# TeensyBreakout.net
KiCad netlist of a schematic drawn in EAGLE
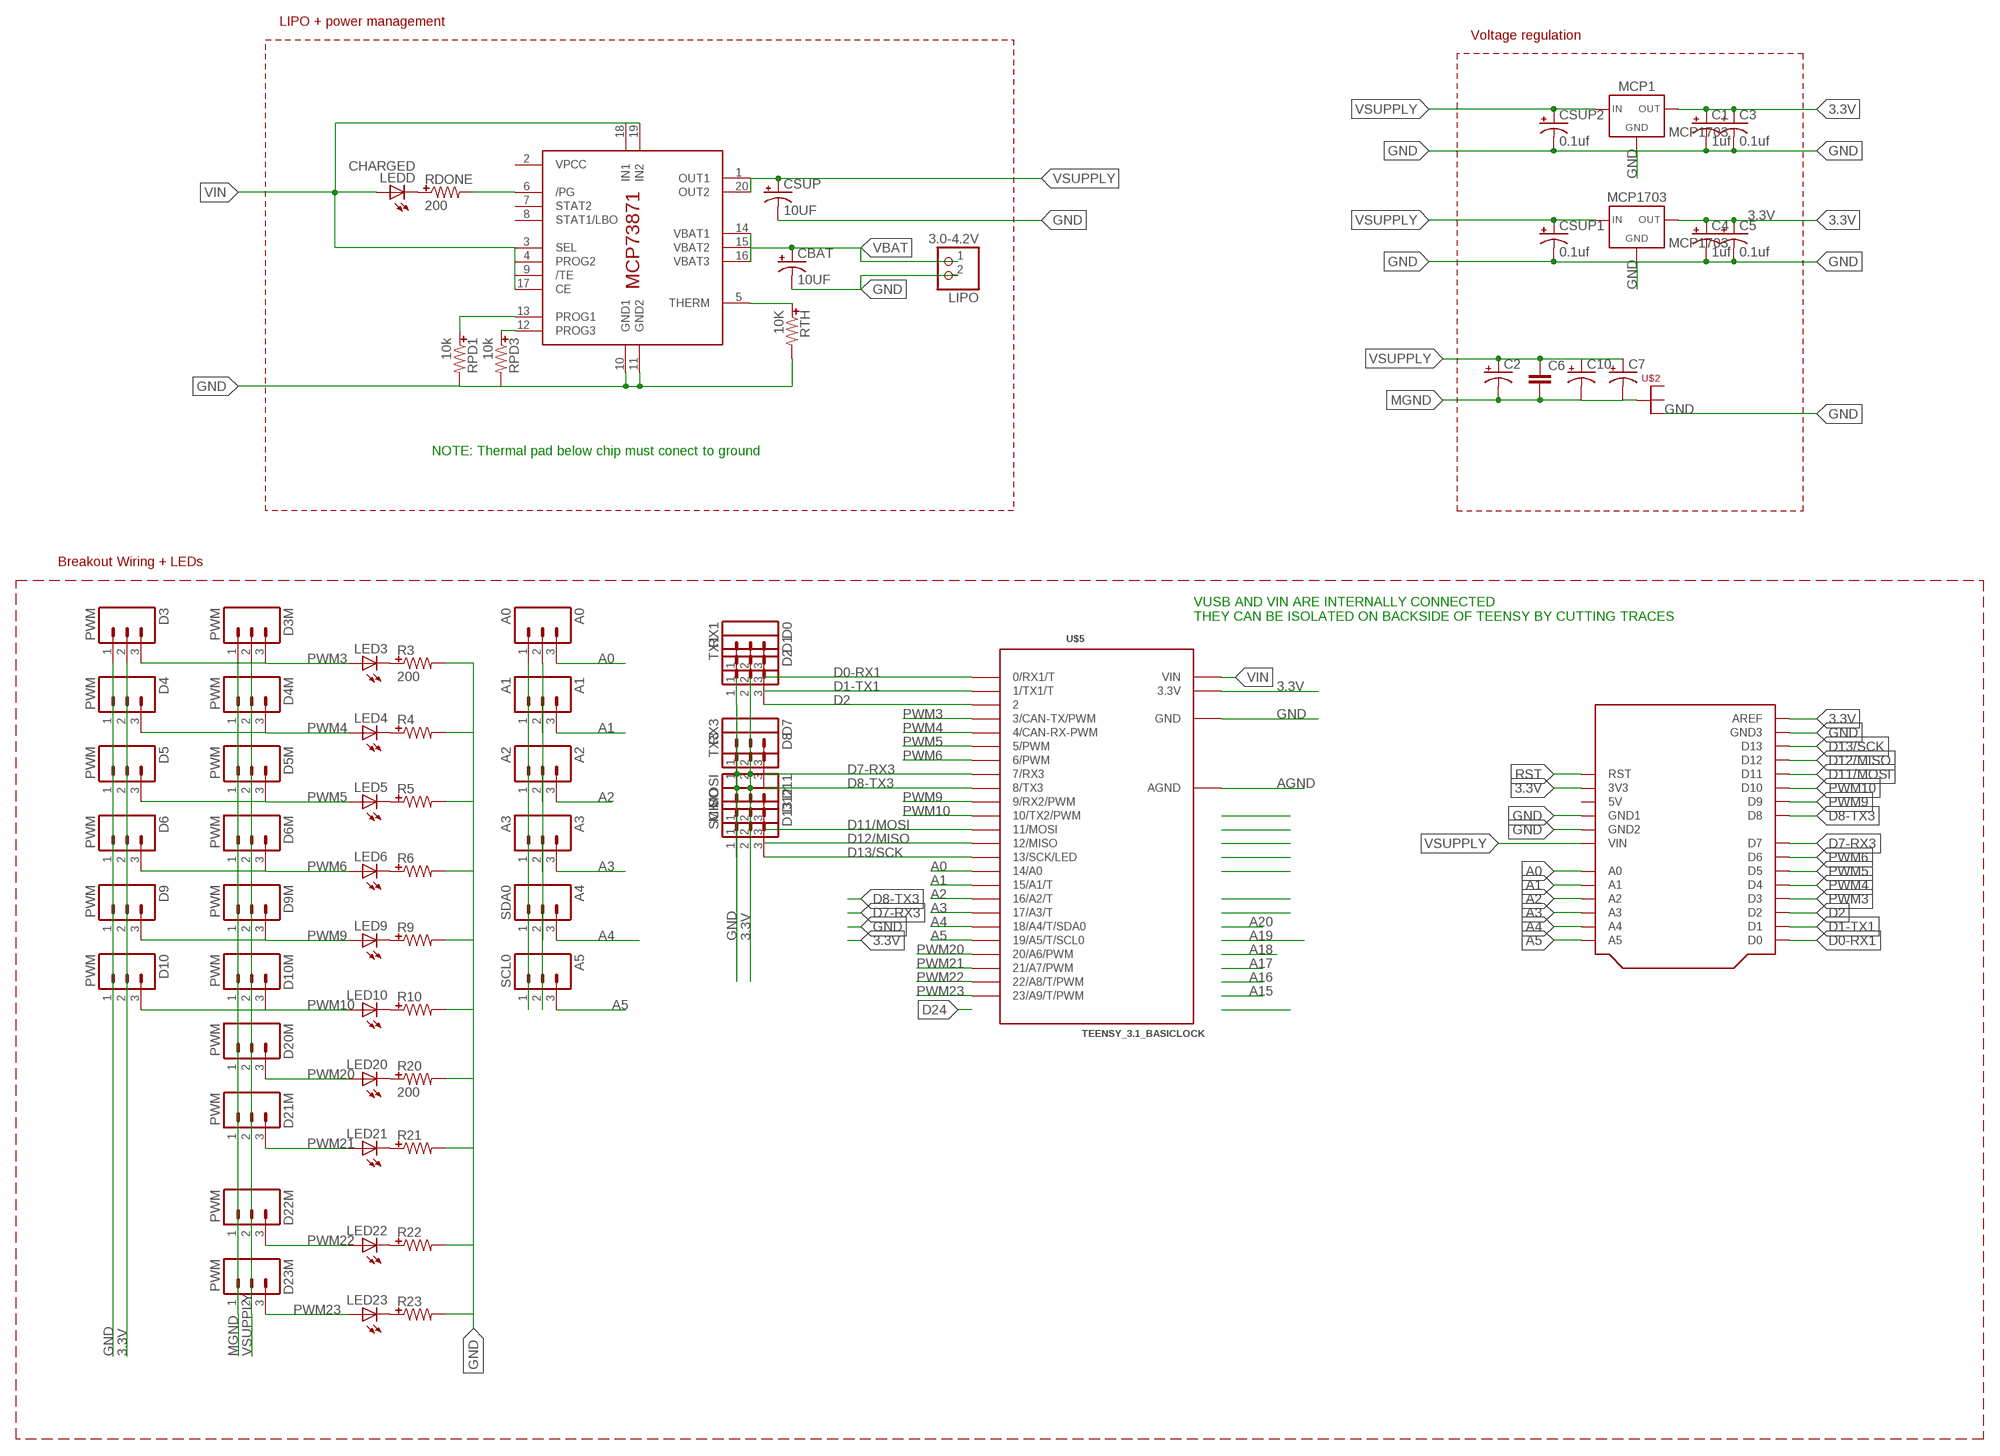
[diagram p0: schematic, sheet 1]

(export (version "E")
  (design (tool "Eeschema 10.0.6"))
  (components
    (comp (ref "A0")
      (value "A0")
      (footprint "eagle-import:1X03_LOCK")
      (libsource (lib "eagle-import") (part "M03LOCK"))
    )
    (comp (ref "A1")
      (value "A1")
      (footprint "eagle-import:1X03_LOCK")
      (libsource (lib "eagle-import") (part "M03LOCK"))
    )
    (comp (ref "A2")
      (value "A2")
      (footprint "eagle-import:1X03_LOCK")
      (libsource (lib "eagle-import") (part "M03LOCK"))
    )
    (comp (ref "A3")
      (value "A3")
      (footprint "eagle-import:1X03_LOCK")
      (libsource (lib "eagle-import") (part "M03LOCK"))
    )
    (comp (ref "A4")
      (value "SDA0")
      (footprint "eagle-import:1X03_LOCK")
      (libsource (lib "eagle-import") (part "M03LOCK"))
    )
    (comp (ref "A5")
      (value "SCL0")
      (footprint "eagle-import:1X03_LOCK")
      (libsource (lib "eagle-import") (part "M03LOCK"))
    )
    (comp (ref "C1")
      (value "1uf")
      (footprint "eagle-import:0402-0603-0805-UNIVERSAL")
      (libsource (lib "eagle-import") (part "CAP-POLARIZEDUNIVERSAL"))
    )
    (comp (ref "C2")
      (value "CAP-POLARIZEDUNIVERSAL")
      (footprint "eagle-import:0402-0603-0805-UNIVERSAL")
      (libsource (lib "eagle-import") (part "CAP-POLARIZEDUNIVERSAL"))
    )
    (comp (ref "C3")
      (value "0.1uf")
      (footprint "eagle-import:0402-0603-0805-UNIVERSAL")
      (libsource (lib "eagle-import") (part "CAP-POLARIZEDUNIVERSAL"))
    )
    (comp (ref "C4")
      (value "1uf")
      (footprint "eagle-import:0402-0603-0805-UNIVERSAL")
      (libsource (lib "eagle-import") (part "CAP-POLARIZEDUNIVERSAL"))
    )
    (comp (ref "C5")
      (value "0.1uf")
      (footprint "eagle-import:0402-0603-0805-UNIVERSAL")
      (libsource (lib "eagle-import") (part "CAP-POLARIZEDUNIVERSAL"))
    )
    (comp (ref "C6")
      (value "CAP1210")
      (footprint "eagle-import:1210")
      (libsource (lib "eagle-import") (part "CAP1210"))
    )
    (comp (ref "C7")
      (value "CAP-POLARIZEDUNIVERSAL")
      (footprint "eagle-import:0402-0603-0805-UNIVERSAL")
      (libsource (lib "eagle-import") (part "CAP-POLARIZEDUNIVERSAL"))
    )
    (comp (ref "C10")
      (value "CAP-POLARIZEDUNIVERSAL")
      (footprint "eagle-import:0402-0603-0805-UNIVERSAL")
      (libsource (lib "eagle-import") (part "CAP-POLARIZEDUNIVERSAL"))
    )
    (comp (ref "CBAT")
      (value "10UF")
      (footprint "eagle-import:0402-0603-0805-UNIVERSAL")
      (libsource (lib "eagle-import") (part "CAP-POLARIZEDUNIVERSAL"))
    )
    (comp (ref "CSUP")
      (value "10UF")
      (footprint "eagle-import:0402-0603-0805-UNIVERSAL")
      (libsource (lib "eagle-import") (part "CAP-POLARIZEDUNIVERSAL"))
    )
    (comp (ref "CSUP1")
      (value "0.1uf")
      (footprint "eagle-import:0402-0603-0805-UNIVERSAL")
      (libsource (lib "eagle-import") (part "CAP-POLARIZEDUNIVERSAL"))
    )
    (comp (ref "CSUP2")
      (value "0.1uf")
      (footprint "eagle-import:0402-0603-0805-UNIVERSAL")
      (libsource (lib "eagle-import") (part "CAP-POLARIZEDUNIVERSAL"))
    )
    (comp (ref "D0")
      (value "RX1")
      (footprint "eagle-import:1X03_LOCK")
      (libsource (lib "eagle-import") (part "M03LOCK"))
    )
    (comp (ref "D1")
      (value "TX1")
      (footprint "eagle-import:1X03_LOCK")
      (libsource (lib "eagle-import") (part "M03LOCK"))
    )
    (comp (ref "D2")
      (value "M03LOCK")
      (footprint "eagle-import:1X03_LOCK")
      (libsource (lib "eagle-import") (part "M03LOCK"))
    )
    (comp (ref "D3")
      (value "PWM")
      (footprint "eagle-import:1X03_LOCK")
      (libsource (lib "eagle-import") (part "M03LOCK"))
    )
    (comp (ref "D3M")
      (value "PWM")
      (footprint "eagle-import:1X03_LOCK")
      (libsource (lib "eagle-import") (part "M03LOCK"))
    )
    (comp (ref "D4")
      (value "PWM")
      (footprint "eagle-import:1X03_LOCK")
      (libsource (lib "eagle-import") (part "M03LOCK"))
    )
    (comp (ref "D4M")
      (value "PWM")
      (footprint "eagle-import:1X03_LOCK")
      (libsource (lib "eagle-import") (part "M03LOCK"))
    )
    (comp (ref "D5")
      (value "PWM")
      (footprint "eagle-import:1X03_LOCK")
      (libsource (lib "eagle-import") (part "M03LOCK"))
    )
    (comp (ref "D5M")
      (value "PWM")
      (footprint "eagle-import:1X03_LOCK")
      (libsource (lib "eagle-import") (part "M03LOCK"))
    )
    (comp (ref "D6")
      (value "PWM")
      (footprint "eagle-import:1X03_LOCK")
      (libsource (lib "eagle-import") (part "M03LOCK"))
    )
    (comp (ref "D6M")
      (value "PWM")
      (footprint "eagle-import:1X03_LOCK")
      (libsource (lib "eagle-import") (part "M03LOCK"))
    )
    (comp (ref "D7")
      (value "RX3")
      (footprint "eagle-import:1X03_LOCK")
      (libsource (lib "eagle-import") (part "M03LOCK"))
    )
    (comp (ref "D8")
      (value "TX3")
      (footprint "eagle-import:1X03_LOCK")
      (libsource (lib "eagle-import") (part "M03LOCK"))
    )
    (comp (ref "D9")
      (value "PWM")
      (footprint "eagle-import:1X03_LOCK")
      (libsource (lib "eagle-import") (part "M03LOCK"))
    )
    (comp (ref "D9M")
      (value "PWM")
      (footprint "eagle-import:1X03_LOCK")
      (libsource (lib "eagle-import") (part "M03LOCK"))
    )
    (comp (ref "D10")
      (value "PWM")
      (footprint "eagle-import:1X03_LOCK")
      (libsource (lib "eagle-import") (part "M03LOCK"))
    )
    (comp (ref "D10M")
      (value "PWM")
      (footprint "eagle-import:1X03_LOCK")
      (libsource (lib "eagle-import") (part "M03LOCK"))
    )
    (comp (ref "D11")
      (value "MOSI")
      (footprint "eagle-import:1X03_LOCK")
      (libsource (lib "eagle-import") (part "M03LOCK"))
    )
    (comp (ref "D12")
      (value "MISO")
      (footprint "eagle-import:1X03_LOCK")
      (libsource (lib "eagle-import") (part "M03LOCK"))
    )
    (comp (ref "D13")
      (value "SCK")
      (footprint "eagle-import:1X03_LOCK")
      (libsource (lib "eagle-import") (part "M03LOCK"))
    )
    (comp (ref "D20M")
      (value "PWM")
      (footprint "eagle-import:1X03_LOCK")
      (libsource (lib "eagle-import") (part "M03LOCK"))
    )
    (comp (ref "D21M")
      (value "PWM")
      (footprint "eagle-import:1X03_LOCK")
      (libsource (lib "eagle-import") (part "M03LOCK"))
    )
    (comp (ref "D22M")
      (value "PWM")
      (footprint "eagle-import:1X03_LOCK")
      (libsource (lib "eagle-import") (part "M03LOCK"))
    )
    (comp (ref "D23M")
      (value "PWM")
      (footprint "eagle-import:1X03_LOCK")
      (libsource (lib "eagle-import") (part "M03LOCK"))
    )
    (comp (ref "IC1")
      (value "MCP73871")
      (footprint "eagle-import:QFN20")
      (libsource (lib "eagle-import") (part "MCP73871"))
    )
    (comp (ref "LED3")
      (value "LEDUNIVERSAL")
      (footprint "eagle-import:0402-0603-0805-UNIVERSAL")
      (libsource (lib "eagle-import") (part "LEDUNIVERSAL"))
    )
    (comp (ref "LED4")
      (value "LEDUNIVERSAL")
      (footprint "eagle-import:0402-0603-0805-UNIVERSAL")
      (libsource (lib "eagle-import") (part "LEDUNIVERSAL"))
    )
    (comp (ref "LED5")
      (value "LEDUNIVERSAL")
      (footprint "eagle-import:0402-0603-0805-UNIVERSAL")
      (libsource (lib "eagle-import") (part "LEDUNIVERSAL"))
    )
    (comp (ref "LED6")
      (value "LEDUNIVERSAL")
      (footprint "eagle-import:0402-0603-0805-UNIVERSAL")
      (libsource (lib "eagle-import") (part "LEDUNIVERSAL"))
    )
    (comp (ref "LED9")
      (value "LEDUNIVERSAL")
      (footprint "eagle-import:0402-0603-0805-UNIVERSAL")
      (libsource (lib "eagle-import") (part "LEDUNIVERSAL"))
    )
    (comp (ref "LED10")
      (value "LEDUNIVERSAL")
      (footprint "eagle-import:0402-0603-0805-UNIVERSAL")
      (libsource (lib "eagle-import") (part "LEDUNIVERSAL"))
    )
    (comp (ref "LED20")
      (value "LEDUNIVERSAL")
      (footprint "eagle-import:0402-0603-0805-UNIVERSAL")
      (libsource (lib "eagle-import") (part "LEDUNIVERSAL"))
    )
    (comp (ref "LED21")
      (value "LEDUNIVERSAL")
      (footprint "eagle-import:0402-0603-0805-UNIVERSAL")
      (libsource (lib "eagle-import") (part "LEDUNIVERSAL"))
    )
    (comp (ref "LED22")
      (value "LEDUNIVERSAL")
      (footprint "eagle-import:0402-0603-0805-UNIVERSAL")
      (libsource (lib "eagle-import") (part "LEDUNIVERSAL"))
    )
    (comp (ref "LED23")
      (value "LEDUNIVERSAL")
      (footprint "eagle-import:0402-0603-0805-UNIVERSAL")
      (libsource (lib "eagle-import") (part "LEDUNIVERSAL"))
    )
    (comp (ref "LEDD")
      (value "CHARGED")
      (footprint "eagle-import:0402-0603-0805-UNIVERSAL")
      (libsource (lib "eagle-import") (part "LEDUNIVERSAL"))
    )
    (comp (ref "LIPO")
      (value "3.0-4.2V")
      (footprint "eagle-import:JST-PH-2-THM-RA")
      (libsource (lib "eagle-import") (part "JST_2PIN-THM-RA"))
    )
    (comp (ref "MCP1")
      (value "MCP1703")
      (footprint "eagle-import:SOT23")
      (libsource (lib "eagle-import") (part "VOLTAGE-REGULATORMCP1703"))
    )
    (comp (ref "MCP1703")
      (value "MCP1703")
      (footprint "eagle-import:SOT23")
      (libsource (lib "eagle-import") (part "VOLTAGE-REGULATORMCP1703"))
    )
    (comp (ref "R3")
      (value "200")
      (footprint "eagle-import:0402-0603-0805-UNIVERSAL")
      (libsource (lib "eagle-import") (part "RESISTORUNIVERSAL"))
    )
    (comp (ref "R4")
      (value "RESISTORUNIVERSAL")
      (footprint "eagle-import:0402-0603-0805-UNIVERSAL")
      (libsource (lib "eagle-import") (part "RESISTORUNIVERSAL"))
    )
    (comp (ref "R5")
      (value "RESISTORUNIVERSAL")
      (footprint "eagle-import:0402-0603-0805-UNIVERSAL")
      (libsource (lib "eagle-import") (part "RESISTORUNIVERSAL"))
    )
    (comp (ref "R6")
      (value "RESISTORUNIVERSAL")
      (footprint "eagle-import:0402-0603-0805-UNIVERSAL")
      (libsource (lib "eagle-import") (part "RESISTORUNIVERSAL"))
    )
    (comp (ref "R9")
      (value "RESISTORUNIVERSAL")
      (footprint "eagle-import:0402-0603-0805-UNIVERSAL")
      (libsource (lib "eagle-import") (part "RESISTORUNIVERSAL"))
    )
    (comp (ref "R10")
      (value "RESISTORUNIVERSAL")
      (footprint "eagle-import:0402-0603-0805-UNIVERSAL")
      (libsource (lib "eagle-import") (part "RESISTORUNIVERSAL"))
    )
    (comp (ref "R20")
      (value "200")
      (footprint "eagle-import:0402-0603-0805-UNIVERSAL")
      (libsource (lib "eagle-import") (part "RESISTORUNIVERSAL"))
    )
    (comp (ref "R21")
      (value "RESISTORUNIVERSAL")
      (footprint "eagle-import:0402-0603-0805-UNIVERSAL")
      (libsource (lib "eagle-import") (part "RESISTORUNIVERSAL"))
    )
    (comp (ref "R22")
      (value "RESISTORUNIVERSAL")
      (footprint "eagle-import:0402-0603-0805-UNIVERSAL")
      (libsource (lib "eagle-import") (part "RESISTORUNIVERSAL"))
    )
    (comp (ref "R23")
      (value "RESISTORUNIVERSAL")
      (footprint "eagle-import:0402-0603-0805-UNIVERSAL")
      (libsource (lib "eagle-import") (part "RESISTORUNIVERSAL"))
    )
    (comp (ref "RDONE")
      (value "200")
      (footprint "eagle-import:0402-0603-0805-UNIVERSAL")
      (libsource (lib "eagle-import") (part "RESISTORUNIVERSAL"))
    )
    (comp (ref "RPD1")
      (value "10k")
      (footprint "eagle-import:0402-0603-0805-UNIVERSAL")
      (libsource (lib "eagle-import") (part "RESISTORUNIVERSAL"))
    )
    (comp (ref "RPD3")
      (value "10k")
      (footprint "eagle-import:0402-0603-0805-UNIVERSAL")
      (libsource (lib "eagle-import") (part "RESISTORUNIVERSAL"))
    )
    (comp (ref "RTH")
      (value "10K")
      (footprint "eagle-import:0402-0603-0805-UNIVERSAL")
      (libsource (lib "eagle-import") (part "RESISTORUNIVERSAL"))
    )
    (comp (ref "U$2")
      (value "NET-JUNCTION8-MIL-DIAMETER")
      (footprint "eagle-import:NET-JUNCTION")
      (libsource (lib "eagle-import") (part "NET-JUNCTION8-MIL-DIAMETER"))
    )
    (comp (ref "U$4")
      (value "ARDUINO")
      (footprint "eagle-import:ARDUINO")
      (libsource (lib "eagle-import") (part "ARDUINO"))
    )
    (comp (ref "U$5")
      (value "TEENSY_3.1_BASICLOCK")
      (footprint "eagle-import:TEENSY_3.1_BASIC_LOCK")
      (libsource (lib "eagle-import") (part "TEENSY_3.1_BASICLOCK"))
    )
  )
  (nets
    (net (code "7") (name "/AGND") (class "Default")
      (node (ref "U$5") (pin "AGND") (pinfunction "AGND_AGND") (pintype "power_in"))
    )
    (net (code "8") (name "/PWM20") (class "Default")
      (node (ref "D20M") (pin "3") (pinfunction "3_3") (pintype "passive"))
      (node (ref "LED20") (pin "+") (pinfunction "A_+") (pintype "passive"))
      (node (ref "U$5") (pin "20/A6") (pinfunction "20/A6/PWM_20/A6") (pintype "bidirectional"))
    )
    (net (code "9") (name "/PWM21") (class "Default")
      (node (ref "D21M") (pin "3") (pinfunction "3_3") (pintype "passive"))
      (node (ref "LED21") (pin "+") (pinfunction "A_+") (pintype "passive"))
      (node (ref "U$5") (pin "21/A7") (pinfunction "21/A7/PWM_21/A7") (pintype "bidirectional"))
    )
    (net (code "10") (name "/PWM22") (class "Default")
      (node (ref "D22M") (pin "3") (pinfunction "3_3") (pintype "passive"))
      (node (ref "LED22") (pin "+") (pinfunction "A_+") (pintype "passive"))
      (node (ref "U$5") (pin "22/A8") (pinfunction "22/A8/T/PWM_22/A8") (pintype "bidirectional"))
    )
    (net (code "11") (name "/PWM23") (class "Default")
      (node (ref "D23M") (pin "3") (pinfunction "3_3") (pintype "passive"))
      (node (ref "LED23") (pin "+") (pinfunction "A_+") (pintype "passive"))
      (node (ref "U$5") (pin "23/A9") (pinfunction "23/A9/T/PWM_23/A9") (pintype "bidirectional"))
    )
    (net (code "12") (name "3.3V") (class "Default")
      (node (ref "A0") (pin "2") (pinfunction "2_2") (pintype "passive"))
      (node (ref "A1") (pin "2") (pinfunction "2_2") (pintype "passive"))
      (node (ref "A2") (pin "2") (pinfunction "2_2") (pintype "passive"))
      (node (ref "A3") (pin "2") (pinfunction "2_2") (pintype "passive"))
      (node (ref "A4") (pin "2") (pinfunction "2_2") (pintype "passive"))
      (node (ref "A5") (pin "2") (pinfunction "2_2") (pintype "passive"))
      (node (ref "C1") (pin "+") (pinfunction "+_+") (pintype "passive"))
      (node (ref "C3") (pin "+") (pinfunction "+_+") (pintype "passive"))
      (node (ref "C4") (pin "+") (pinfunction "+_+") (pintype "passive"))
      (node (ref "C5") (pin "+") (pinfunction "+_+") (pintype "passive"))
      (node (ref "D0") (pin "2") (pinfunction "2_2") (pintype "passive"))
      (node (ref "D1") (pin "2") (pinfunction "2_2") (pintype "passive"))
      (node (ref "D10") (pin "2") (pinfunction "2_2") (pintype "passive"))
      (node (ref "D11") (pin "2") (pinfunction "2_2") (pintype "passive"))
      (node (ref "D12") (pin "2") (pinfunction "2_2") (pintype "passive"))
      (node (ref "D13") (pin "2") (pinfunction "2_2") (pintype "passive"))
      (node (ref "D2") (pin "2") (pinfunction "2_2") (pintype "passive"))
      (node (ref "D3") (pin "2") (pinfunction "2_2") (pintype "passive"))
      (node (ref "D4") (pin "2") (pinfunction "2_2") (pintype "passive"))
      (node (ref "D5") (pin "2") (pinfunction "2_2") (pintype "passive"))
      (node (ref "D6") (pin "2") (pinfunction "2_2") (pintype "passive"))
      (node (ref "D7") (pin "2") (pinfunction "2_2") (pintype "passive"))
      (node (ref "D8") (pin "2") (pinfunction "2_2") (pintype "passive"))
      (node (ref "D9") (pin "2") (pinfunction "2_2") (pintype "passive"))
      (node (ref "MCP1") (pin "2") (pinfunction "OUT_2") (pintype "input"))
      (node (ref "MCP1703") (pin "2") (pinfunction "OUT_2") (pintype "input"))
      (node (ref "U$4") (pin "3V3") (pinfunction "3V3_3V3") (pintype "bidirectional"))
      (node (ref "U$4") (pin "AREF") (pinfunction "AREF_AREF") (pintype "bidirectional"))
      (node (ref "U$5") (pin "3.3V") (pinfunction "3.3V_3.3V") (pintype "power_in"))
    )
    (net (code "13") (name "A0") (class "Default")
      (node (ref "A0") (pin "3") (pinfunction "3_3") (pintype "passive"))
      (node (ref "U$4") (pin "A0") (pinfunction "A0_A0") (pintype "bidirectional"))
      (node (ref "U$5") (pin "14/A0") (pinfunction "14/A0_14/A0") (pintype "bidirectional"))
    )
    (net (code "14") (name "A1") (class "Default")
      (node (ref "A1") (pin "3") (pinfunction "3_3") (pintype "passive"))
      (node (ref "U$4") (pin "A1") (pinfunction "A1_A1") (pintype "bidirectional"))
      (node (ref "U$5") (pin "15/A1") (pinfunction "15/A1/T_15/A1") (pintype "bidirectional"))
    )
    (net (code "15") (name "A2") (class "Default")
      (node (ref "A2") (pin "3") (pinfunction "3_3") (pintype "passive"))
      (node (ref "U$4") (pin "A2") (pinfunction "A2_A2") (pintype "bidirectional"))
      (node (ref "U$5") (pin "16/A2") (pinfunction "16/A2/T_16/A2") (pintype "bidirectional"))
    )
    (net (code "16") (name "A3") (class "Default")
      (node (ref "A3") (pin "3") (pinfunction "3_3") (pintype "passive"))
      (node (ref "U$4") (pin "A3") (pinfunction "A3_A3") (pintype "bidirectional"))
      (node (ref "U$5") (pin "17/A3") (pinfunction "17/A3/T_17/A3") (pintype "bidirectional"))
    )
    (net (code "17") (name "A4") (class "Default")
      (node (ref "A4") (pin "3") (pinfunction "3_3") (pintype "passive"))
      (node (ref "U$4") (pin "A4") (pinfunction "A4_A4") (pintype "bidirectional"))
      (node (ref "U$5") (pin "18/A4") (pinfunction "18/A4/T/SDA0_18/A4") (pintype "bidirectional"))
    )
    (net (code "18") (name "A5") (class "Default")
      (node (ref "A5") (pin "3") (pinfunction "3_3") (pintype "passive"))
      (node (ref "U$4") (pin "A5") (pinfunction "A5_A5") (pintype "bidirectional"))
      (node (ref "U$5") (pin "19/A5") (pinfunction "19/A5/T/SCL0_19/A5") (pintype "bidirectional"))
    )
    (net (code "19") (name "D0-RX1") (class "Default")
      (node (ref "D0") (pin "3") (pinfunction "3_3") (pintype "passive"))
      (node (ref "U$4") (pin "D0") (pinfunction "D0_D0") (pintype "bidirectional"))
      (node (ref "U$5") (pin "0") (pinfunction "0/RX1/T_0") (pintype "bidirectional"))
    )
    (net (code "20") (name "D1-TX1") (class "Default")
      (node (ref "D1") (pin "3") (pinfunction "3_3") (pintype "passive"))
      (node (ref "U$4") (pin "D1") (pinfunction "D1_D1") (pintype "bidirectional"))
      (node (ref "U$5") (pin "1") (pinfunction "1/TX1/T_1") (pintype "bidirectional"))
    )
    (net (code "21") (name "D2") (class "Default")
      (node (ref "D2") (pin "3") (pinfunction "3_3") (pintype "passive"))
      (node (ref "U$4") (pin "D2") (pinfunction "D2_D2") (pintype "bidirectional"))
      (node (ref "U$5") (pin "2") (pinfunction "2_2") (pintype "bidirectional"))
    )
    (net (code "22") (name "D7-RX3") (class "Default")
      (node (ref "D7") (pin "3") (pinfunction "3_3") (pintype "passive"))
      (node (ref "U$4") (pin "D7") (pinfunction "D7_D7") (pintype "bidirectional"))
      (node (ref "U$5") (pin "7") (pinfunction "7/RX3_7") (pintype "bidirectional"))
    )
    (net (code "23") (name "D8-TX3") (class "Default")
      (node (ref "D8") (pin "3") (pinfunction "3_3") (pintype "passive"))
      (node (ref "U$4") (pin "D8") (pinfunction "D8_D8") (pintype "bidirectional"))
      (node (ref "U$5") (pin "8") (pinfunction "8/TX3_8") (pintype "bidirectional"))
    )
    (net (code "24") (name "D11{slash}MOSI") (class "Default")
      (node (ref "D11") (pin "3") (pinfunction "3_3") (pintype "passive"))
      (node (ref "U$4") (pin "D11") (pinfunction "D11_D11") (pintype "bidirectional"))
      (node (ref "U$5") (pin "11") (pinfunction "11/MOSI_11") (pintype "bidirectional"))
    )
    (net (code "25") (name "D12{slash}MISO") (class "Default")
      (node (ref "D12") (pin "3") (pinfunction "3_3") (pintype "passive"))
      (node (ref "U$4") (pin "D12") (pinfunction "D12_D12") (pintype "bidirectional"))
      (node (ref "U$5") (pin "12") (pinfunction "12/MISO_12") (pintype "bidirectional"))
    )
    (net (code "26") (name "D13{slash}SCK") (class "Default")
      (node (ref "D13") (pin "3") (pinfunction "3_3") (pintype "passive"))
      (node (ref "U$4") (pin "D13") (pinfunction "D13_D13") (pintype "bidirectional"))
      (node (ref "U$5") (pin "13") (pinfunction "13/SCK/LED_13") (pintype "bidirectional"))
    )
    (net (code "28") (name "GND") (class "Default")
      (node (ref "A0") (pin "1") (pinfunction "1_1") (pintype "passive"))
      (node (ref "A1") (pin "1") (pinfunction "1_1") (pintype "passive"))
      (node (ref "A2") (pin "1") (pinfunction "1_1") (pintype "passive"))
      (node (ref "A3") (pin "1") (pinfunction "1_1") (pintype "passive"))
      (node (ref "A4") (pin "1") (pinfunction "1_1") (pintype "passive"))
      (node (ref "A5") (pin "1") (pinfunction "1_1") (pintype "passive"))
      (node (ref "C1") (pin "-") (pinfunction "-_-") (pintype "passive"))
      (node (ref "C3") (pin "-") (pinfunction "-_-") (pintype "passive"))
      (node (ref "C4") (pin "-") (pinfunction "-_-") (pintype "passive"))
      (node (ref "C5") (pin "-") (pinfunction "-_-") (pintype "passive"))
      (node (ref "CBAT") (pin "-") (pinfunction "-_-") (pintype "passive"))
      (node (ref "CSUP") (pin "-") (pinfunction "-_-") (pintype "passive"))
      (node (ref "CSUP1") (pin "-") (pinfunction "-_-") (pintype "passive"))
      (node (ref "CSUP2") (pin "-") (pinfunction "-_-") (pintype "passive"))
      (node (ref "D0") (pin "1") (pinfunction "1_1") (pintype "passive"))
      (node (ref "D1") (pin "1") (pinfunction "1_1") (pintype "passive"))
      (node (ref "D10") (pin "1") (pinfunction "1_1") (pintype "passive"))
      (node (ref "D11") (pin "1") (pinfunction "1_1") (pintype "passive"))
      (node (ref "D12") (pin "1") (pinfunction "1_1") (pintype "passive"))
      (node (ref "D13") (pin "1") (pinfunction "1_1") (pintype "passive"))
      (node (ref "D2") (pin "1") (pinfunction "1_1") (pintype "passive"))
      (node (ref "D3") (pin "1") (pinfunction "1_1") (pintype "passive"))
      (node (ref "D4") (pin "1") (pinfunction "1_1") (pintype "passive"))
      (node (ref "D5") (pin "1") (pinfunction "1_1") (pintype "passive"))
      (node (ref "D6") (pin "1") (pinfunction "1_1") (pintype "passive"))
      (node (ref "D7") (pin "1") (pinfunction "1_1") (pintype "passive"))
      (node (ref "D8") (pin "1") (pinfunction "1_1") (pintype "passive"))
      (node (ref "D9") (pin "1") (pinfunction "1_1") (pintype "passive"))
      (node (ref "IC1") (pin "10") (pinfunction "GND1_10") (pintype "power_in"))
      (node (ref "IC1") (pin "11") (pinfunction "GND2_11") (pintype "power_in"))
      (node (ref "LIPO") (pin "2") (pinfunction "1_2") (pintype "passive"))
      (node (ref "MCP1") (pin "1") (pinfunction "GND_1") (pintype "input"))
      (node (ref "MCP1703") (pin "1") (pinfunction "GND_1") (pintype "input"))
      (node (ref "R10") (pin "-") (pinfunction "2_-") (pintype "passive"))
      (node (ref "R20") (pin "-") (pinfunction "2_-") (pintype "passive"))
      (node (ref "R21") (pin "-") (pinfunction "2_-") (pintype "passive"))
      (node (ref "R22") (pin "-") (pinfunction "2_-") (pintype "passive"))
      (node (ref "R23") (pin "-") (pinfunction "2_-") (pintype "passive"))
      (node (ref "R3") (pin "-") (pinfunction "2_-") (pintype "passive"))
      (node (ref "R4") (pin "-") (pinfunction "2_-") (pintype "passive"))
      (node (ref "R5") (pin "-") (pinfunction "2_-") (pintype "passive"))
      (node (ref "R6") (pin "-") (pinfunction "2_-") (pintype "passive"))
      (node (ref "R9") (pin "-") (pinfunction "2_-") (pintype "passive"))
      (node (ref "RPD1") (pin "-") (pinfunction "2_-") (pintype "passive"))
      (node (ref "RPD3") (pin "-") (pinfunction "2_-") (pintype "passive"))
      (node (ref "RTH") (pin "-") (pinfunction "2_-") (pintype "passive"))
      (node (ref "U$2") (pin "P$4") (pinfunction "3_P$4") (pintype "bidirectional"))
      (node (ref "U$4") (pin "GND1") (pinfunction "GND1_GND1") (pintype "bidirectional"))
      (node (ref "U$4") (pin "GND2") (pinfunction "GND2_GND2") (pintype "bidirectional"))
      (node (ref "U$4") (pin "GND3") (pinfunction "GND3_GND3") (pintype "bidirectional"))
      (node (ref "U$5") (pin "GND") (pinfunction "GND_GND") (pintype "power_in"))
    )
    (net (code "29") (name "MGND") (class "Default")
      (node (ref "C10") (pin "-") (pinfunction "-_-") (pintype "passive"))
      (node (ref "C2") (pin "-") (pinfunction "-_-") (pintype "passive"))
      (node (ref "C6") (pin "2") (pinfunction "2_2") (pintype "passive"))
      (node (ref "C7") (pin "-") (pinfunction "-_-") (pintype "passive"))
      (node (ref "D10M") (pin "1") (pinfunction "1_1") (pintype "passive"))
      (node (ref "D20M") (pin "1") (pinfunction "1_1") (pintype "passive"))
      (node (ref "D21M") (pin "1") (pinfunction "1_1") (pintype "passive"))
      (node (ref "D22M") (pin "1") (pinfunction "1_1") (pintype "passive"))
      (node (ref "D23M") (pin "1") (pinfunction "1_1") (pintype "passive"))
      (node (ref "D3M") (pin "1") (pinfunction "1_1") (pintype "passive"))
      (node (ref "D4M") (pin "1") (pinfunction "1_1") (pintype "passive"))
      (node (ref "D5M") (pin "1") (pinfunction "1_1") (pintype "passive"))
      (node (ref "D6M") (pin "1") (pinfunction "1_1") (pintype "passive"))
      (node (ref "D9M") (pin "1") (pinfunction "1_1") (pintype "passive"))
      (node (ref "U$2") (pin "P$1") (pinfunction "1_P$1") (pintype "bidirectional"))
    )
    (net (code "30") (name "Net-(IC1-PROG1)") (class "Default")
      (node (ref "IC1") (pin "13") (pinfunction "PROG1_13") (pintype "input"))
      (node (ref "RPD1") (pin "+") (pinfunction "1_+") (pintype "passive"))
    )
    (net (code "31") (name "Net-(IC1-PROG3)") (class "Default")
      (node (ref "IC1") (pin "12") (pinfunction "PROG3_12") (pintype "input"))
      (node (ref "RPD3") (pin "+") (pinfunction "1_+") (pintype "passive"))
    )
    (net (code "32") (name "Net-(IC1-THERM)") (class "Default")
      (node (ref "IC1") (pin "5") (pinfunction "THERM_5") (pintype "input"))
      (node (ref "RTH") (pin "+") (pinfunction "1_+") (pintype "passive"))
    )
    (net (code "33") (name "Net-(IC1-{slash}PG)") (class "Default")
      (node (ref "IC1") (pin "6") (pinfunction "/PG_6") (pintype "output"))
      (node (ref "RDONE") (pin "-") (pinfunction "2_-") (pintype "passive"))
    )
    (net (code "34") (name "Net-(LED3-C)") (class "Default")
      (node (ref "LED3") (pin "-") (pinfunction "C_-") (pintype "passive"))
      (node (ref "R3") (pin "+") (pinfunction "1_+") (pintype "passive"))
    )
    (net (code "35") (name "Net-(LED4-C)") (class "Default")
      (node (ref "LED4") (pin "-") (pinfunction "C_-") (pintype "passive"))
      (node (ref "R4") (pin "+") (pinfunction "1_+") (pintype "passive"))
    )
    (net (code "36") (name "Net-(LED5-C)") (class "Default")
      (node (ref "LED5") (pin "-") (pinfunction "C_-") (pintype "passive"))
      (node (ref "R5") (pin "+") (pinfunction "1_+") (pintype "passive"))
    )
    (net (code "37") (name "Net-(LED6-C)") (class "Default")
      (node (ref "LED6") (pin "-") (pinfunction "C_-") (pintype "passive"))
      (node (ref "R6") (pin "+") (pinfunction "1_+") (pintype "passive"))
    )
    (net (code "38") (name "Net-(LED9-C)") (class "Default")
      (node (ref "LED9") (pin "-") (pinfunction "C_-") (pintype "passive"))
      (node (ref "R9") (pin "+") (pinfunction "1_+") (pintype "passive"))
    )
    (net (code "39") (name "Net-(LED10-C)") (class "Default")
      (node (ref "LED10") (pin "-") (pinfunction "C_-") (pintype "passive"))
      (node (ref "R10") (pin "+") (pinfunction "1_+") (pintype "passive"))
    )
    (net (code "40") (name "Net-(LED20-C)") (class "Default")
      (node (ref "LED20") (pin "-") (pinfunction "C_-") (pintype "passive"))
      (node (ref "R20") (pin "+") (pinfunction "1_+") (pintype "passive"))
    )
    (net (code "41") (name "Net-(LED21-C)") (class "Default")
      (node (ref "LED21") (pin "-") (pinfunction "C_-") (pintype "passive"))
      (node (ref "R21") (pin "+") (pinfunction "1_+") (pintype "passive"))
    )
    (net (code "42") (name "Net-(LED22-C)") (class "Default")
      (node (ref "LED22") (pin "-") (pinfunction "C_-") (pintype "passive"))
      (node (ref "R22") (pin "+") (pinfunction "1_+") (pintype "passive"))
    )
    (net (code "43") (name "Net-(LED23-C)") (class "Default")
      (node (ref "LED23") (pin "-") (pinfunction "C_-") (pintype "passive"))
      (node (ref "R23") (pin "+") (pinfunction "1_+") (pintype "passive"))
    )
    (net (code "44") (name "Net-(LEDD-C)") (class "Default")
      (node (ref "LEDD") (pin "-") (pinfunction "C_-") (pintype "passive"))
      (node (ref "RDONE") (pin "+") (pinfunction "1_+") (pintype "passive"))
    )
    (net (code "45") (name "PWM3") (class "Default")
      (node (ref "D3") (pin "3") (pinfunction "3_3") (pintype "passive"))
      (node (ref "D3M") (pin "3") (pinfunction "3_3") (pintype "passive"))
      (node (ref "LED3") (pin "+") (pinfunction "A_+") (pintype "passive"))
      (node (ref "U$4") (pin "D3") (pinfunction "D3_D3") (pintype "bidirectional"))
      (node (ref "U$5") (pin "3") (pinfunction "3/CAN-TX/PWM_3") (pintype "bidirectional"))
    )
    (net (code "46") (name "PWM4") (class "Default")
      (node (ref "D4") (pin "3") (pinfunction "3_3") (pintype "passive"))
      (node (ref "D4M") (pin "3") (pinfunction "3_3") (pintype "passive"))
      (node (ref "LED4") (pin "+") (pinfunction "A_+") (pintype "passive"))
      (node (ref "U$4") (pin "D4") (pinfunction "D4_D4") (pintype "bidirectional"))
      (node (ref "U$5") (pin "4") (pinfunction "4/CAN-RX-PWM_4") (pintype "bidirectional"))
    )
    (net (code "47") (name "PWM5") (class "Default")
      (node (ref "D5") (pin "3") (pinfunction "3_3") (pintype "passive"))
      (node (ref "D5M") (pin "3") (pinfunction "3_3") (pintype "passive"))
      (node (ref "LED5") (pin "+") (pinfunction "A_+") (pintype "passive"))
      (node (ref "U$4") (pin "D5") (pinfunction "D5_D5") (pintype "bidirectional"))
      (node (ref "U$5") (pin "5") (pinfunction "5/PWM_5") (pintype "bidirectional"))
    )
    (net (code "48") (name "PWM6") (class "Default")
      (node (ref "D6") (pin "3") (pinfunction "3_3") (pintype "passive"))
      (node (ref "D6M") (pin "3") (pinfunction "3_3") (pintype "passive"))
      (node (ref "LED6") (pin "+") (pinfunction "A_+") (pintype "passive"))
      (node (ref "U$4") (pin "D6") (pinfunction "D6_D6") (pintype "bidirectional"))
      (node (ref "U$5") (pin "6") (pinfunction "6/PWM_6") (pintype "bidirectional"))
    )
    (net (code "49") (name "PWM9") (class "Default")
      (node (ref "D9") (pin "3") (pinfunction "3_3") (pintype "passive"))
      (node (ref "D9M") (pin "3") (pinfunction "3_3") (pintype "passive"))
      (node (ref "LED9") (pin "+") (pinfunction "A_+") (pintype "passive"))
      (node (ref "U$4") (pin "D9") (pinfunction "D9_D9") (pintype "bidirectional"))
      (node (ref "U$5") (pin "9") (pinfunction "9/RX2/PWM_9") (pintype "bidirectional"))
    )
    (net (code "50") (name "PWM10") (class "Default")
      (node (ref "D10") (pin "3") (pinfunction "3_3") (pintype "passive"))
      (node (ref "D10M") (pin "3") (pinfunction "3_3") (pintype "passive"))
      (node (ref "LED10") (pin "+") (pinfunction "A_+") (pintype "passive"))
      (node (ref "U$4") (pin "D10") (pinfunction "D10_D10") (pintype "bidirectional"))
      (node (ref "U$5") (pin "10") (pinfunction "10/TX2/PWM_10") (pintype "bidirectional"))
    )
    (net (code "51") (name "RST") (class "Default")
      (node (ref "U$4") (pin "RST") (pinfunction "RST_RST") (pintype "bidirectional"))
    )
    (net (code "52") (name "VBAT") (class "Default")
      (node (ref "CBAT") (pin "+") (pinfunction "+_+") (pintype "passive"))
      (node (ref "IC1") (pin "14") (pinfunction "VBAT1_14") (pintype "output"))
      (node (ref "IC1") (pin "15") (pinfunction "VBAT2_15") (pintype "output"))
      (node (ref "IC1") (pin "16") (pinfunction "VBAT3_16") (pintype "output"))
      (node (ref "LIPO") (pin "1") (pinfunction "2_1") (pintype "passive"))
    )
    (net (code "53") (name "VIN") (class "Default")
      (node (ref "IC1") (pin "17") (pinfunction "CE_17") (pintype "input"))
      (node (ref "IC1") (pin "18") (pinfunction "IN1_18") (pintype "input"))
      (node (ref "IC1") (pin "19") (pinfunction "IN2_19") (pintype "input"))
      (node (ref "IC1") (pin "3") (pinfunction "SEL_3") (pintype "input"))
      (node (ref "IC1") (pin "4") (pinfunction "PROG2_4") (pintype "input"))
      (node (ref "IC1") (pin "9") (pinfunction "/TE_9") (pintype "input"))
      (node (ref "LEDD") (pin "+") (pinfunction "A_+") (pintype "passive"))
      (node (ref "U$5") (pin "VIN") (pinfunction "VIN_VIN") (pintype "power_in"))
    )
    (net (code "54") (name "VSUPPLY") (class "Default")
      (node (ref "C10") (pin "+") (pinfunction "+_+") (pintype "passive"))
      (node (ref "C2") (pin "+") (pinfunction "+_+") (pintype "passive"))
      (node (ref "C6") (pin "1") (pinfunction "1_1") (pintype "passive"))
      (node (ref "C7") (pin "+") (pinfunction "+_+") (pintype "passive"))
      (node (ref "CSUP") (pin "+") (pinfunction "+_+") (pintype "passive"))
      (node (ref "CSUP1") (pin "+") (pinfunction "+_+") (pintype "passive"))
      (node (ref "CSUP2") (pin "+") (pinfunction "+_+") (pintype "passive"))
      (node (ref "D10M") (pin "2") (pinfunction "2_2") (pintype "passive"))
      (node (ref "D20M") (pin "2") (pinfunction "2_2") (pintype "passive"))
      (node (ref "D21M") (pin "2") (pinfunction "2_2") (pintype "passive"))
      (node (ref "D22M") (pin "2") (pinfunction "2_2") (pintype "passive"))
      (node (ref "D23M") (pin "2") (pinfunction "2_2") (pintype "passive"))
      (node (ref "D3M") (pin "2") (pinfunction "2_2") (pintype "passive"))
      (node (ref "D4M") (pin "2") (pinfunction "2_2") (pintype "passive"))
      (node (ref "D5M") (pin "2") (pinfunction "2_2") (pintype "passive"))
      (node (ref "D6M") (pin "2") (pinfunction "2_2") (pintype "passive"))
      (node (ref "D9M") (pin "2") (pinfunction "2_2") (pintype "passive"))
      (node (ref "IC1") (pin "1") (pinfunction "OUT1_1") (pintype "output"))
      (node (ref "IC1") (pin "20") (pinfunction "OUT2_20") (pintype "output"))
      (node (ref "MCP1") (pin "3") (pinfunction "IN_3") (pintype "input"))
      (node (ref "MCP1703") (pin "3") (pinfunction "IN_3") (pintype "input"))
      (node (ref "U$4") (pin "VIN") (pinfunction "VIN_VIN") (pintype "bidirectional"))
    )
    (net (code "55") (name "unconnected-(IC1-STAT1{slash}LBO-Pad8)") (class "Default")
      (node (ref "IC1") (pin "8") (pinfunction "STAT1/LBO_8") (pintype "output"))
    )
    (net (code "56") (name "unconnected-(IC1-STAT2-Pad7)") (class "Default")
      (node (ref "IC1") (pin "7") (pinfunction "STAT2_7") (pintype "output"))
    )
    (net (code "57") (name "unconnected-(IC1-VPCC-Pad2)") (class "Default")
      (node (ref "IC1") (pin "2") (pinfunction "VPCC_2") (pintype "input"))
    )
    (net (code "58") (name "unconnected-(U$2-2-PadP$3)") (class "Default")
      (node (ref "U$2") (pin "P$3") (pinfunction "2_P$3") (pintype "bidirectional"))
    )
    (net (code "59") (name "unconnected-(U$2-4-PadP$5)") (class "Default")
      (node (ref "U$2") (pin "P$5") (pinfunction "4_P$5") (pintype "bidirectional"))
    )
    (net (code "60") (name "unconnected-(U$4-Pad5V)") (class "Default")
      (node (ref "U$4") (pin "5V") (pinfunction "5V_5V") (pintype "bidirectional"))
    )
  )
)
